# BabyBeat.net
KiCad netlist of a schematic drawn in EAGLE
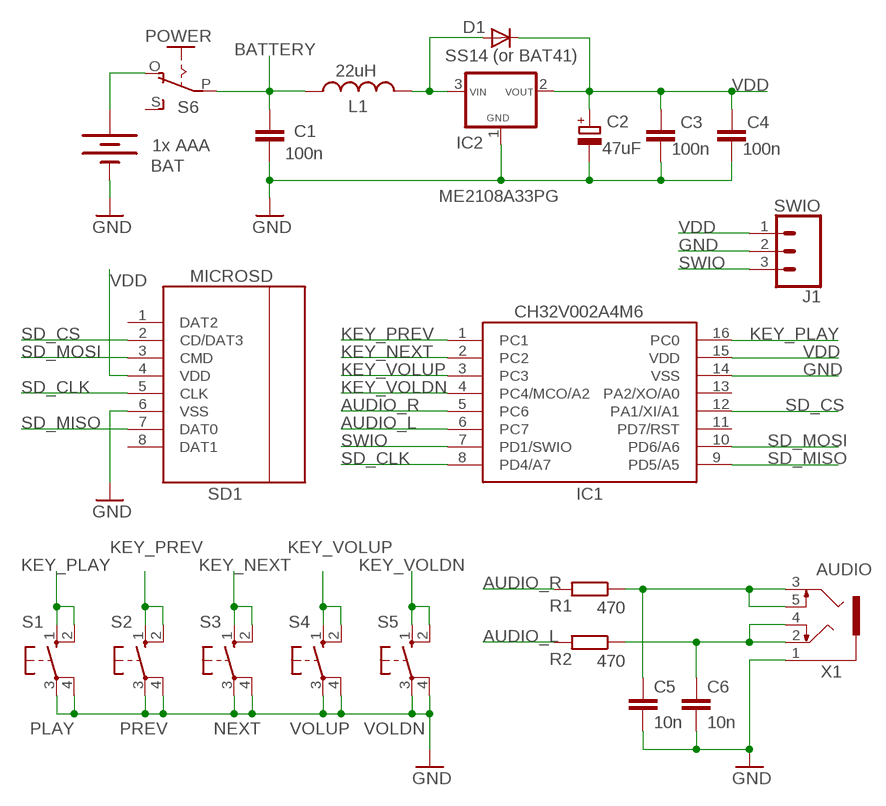
[diagram p0: schematic, sheet 1]

(export (version "E")
  (design (tool "Eeschema 10.0.6"))
  (components
    (comp (ref "BAT")
      (value "1x AAA")
      (footprint "eagle-import:BATTERY-AAA-KIT")
      (libsource (lib "eagle-import") (part "BATTERY-AAA_KIT"))
    )
    (comp (ref "C1")
      (value "100n")
      (footprint "eagle-import:C1206K")
      (libsource (lib "eagle-import") (part "C-EUC1206K"))
    )
    (comp (ref "C2")
      (value "47uF")
      (footprint "eagle-import:140CLH-0810")
      (libsource (lib "eagle-import") (part "CPOL-EU140CLH-0810"))
    )
    (comp (ref "C3")
      (value "100n")
      (footprint "eagle-import:C1206K")
      (libsource (lib "eagle-import") (part "C-EUC1206K"))
    )
    (comp (ref "C4")
      (value "100n")
      (footprint "eagle-import:C1206K")
      (libsource (lib "eagle-import") (part "C-EUC1206K"))
    )
    (comp (ref "C5")
      (value "10n")
      (footprint "eagle-import:C1206K")
      (libsource (lib "eagle-import") (part "C-EUC1206K"))
    )
    (comp (ref "C6")
      (value "10n")
      (footprint "eagle-import:C1206K")
      (libsource (lib "eagle-import") (part "C-EUC1206K"))
    )
    (comp (ref "D1")
      (value "SS14 (or BAT41)")
      (footprint "eagle-import:SOD-123_MINI-SMA")
      (libsource (lib "eagle-import") (part "CGRM400-G1"))
    )
    (comp (ref "IC1")
      (value "CH32V002A4M6")
      (footprint "eagle-import:SOP16")
      (libsource (lib "eagle-import") (part "CH32V002A4M6"))
    )
    (comp (ref "IC2")
      (value "ME2108A33PG")
      (footprint "eagle-import:SOT89-R")
      (libsource (lib "eagle-import") (part "ME2108A33PG"))
    )
    (comp (ref "J1")
      (value "SWIO")
      (footprint "eagle-import:1X03_LONGPADS")
      (libsource (lib "eagle-import") (part "CONN_03LONGPADS"))
    )
    (comp (ref "L1")
      (value "22uH")
      (footprint "eagle-import:POWER-CHOKE_WE-TPC")
      (libsource (lib "eagle-import") (part "L-USWE-TPC"))
    )
    (comp (ref "R1")
      (value "470")
      (footprint "eagle-import:M1206")
      (libsource (lib "eagle-import") (part "R-EU_M1206"))
    )
    (comp (ref "R2")
      (value "470")
      (footprint "eagle-import:M1206")
      (libsource (lib "eagle-import") (part "R-EU_M1206"))
    )
    (comp (ref "S1")
      (value "PLAY")
      (footprint "eagle-import:B3F-10XX")
      (fields (field (name "MPN") "B3F-1000"))
      (libsource (lib "eagle-import") (part "10-XX"))
    )
    (comp (ref "S2")
      (value "PREV")
      (footprint "eagle-import:B3F-10XX")
      (fields (field (name "MPN") "B3F-1000"))
      (libsource (lib "eagle-import") (part "10-XX"))
    )
    (comp (ref "S3")
      (value "NEXT")
      (footprint "eagle-import:B3F-10XX")
      (fields (field (name "MPN") "B3F-1000"))
      (libsource (lib "eagle-import") (part "10-XX"))
    )
    (comp (ref "S4")
      (value "VOLUP")
      (footprint "eagle-import:B3F-10XX")
      (fields (field (name "MPN") "B3F-1000"))
      (libsource (lib "eagle-import") (part "10-XX"))
    )
    (comp (ref "S5")
      (value "VOLDN")
      (footprint "eagle-import:B3F-10XX")
      (fields (field (name "MPN") "B3F-1000"))
      (libsource (lib "eagle-import") (part "10-XX"))
    )
    (comp (ref "S6")
      (value "POWER")
      (footprint "eagle-import:EG1218")
      (libsource (lib "eagle-import") (part "EG1218S"))
    )
    (comp (ref "SD1")
      (value "MICROSD")
      (footprint "eagle-import:MICROSD")
      (libsource (lib "eagle-import") (part "MICROSD"))
    )
    (comp (ref "X1")
      (value "AUDIO")
      (footprint "eagle-import:1503_09")
      (libsource (lib "eagle-import") (part "1503_09"))
    )
  )
  (nets
    (net (code "1") (name "/AUDIO_L") (class "Default")
      (node (ref "IC1") (pin "6") (pinfunction "PC7_6") (pintype "bidirectional"))
      (node (ref "R2") (pin "2") (pinfunction "2_2") (pintype "passive"))
    )
    (net (code "2") (name "/AUDIO_R") (class "Default")
      (node (ref "IC1") (pin "5") (pinfunction "PC6_5") (pintype "bidirectional"))
      (node (ref "R1") (pin "2") (pinfunction "2_2") (pintype "passive"))
    )
    (net (code "3") (name "/BATTERY") (class "Default")
      (node (ref "C1") (pin "1") (pinfunction "1_1") (pintype "passive"))
      (node (ref "L1") (pin "1") (pinfunction "1_1") (pintype "passive"))
      (node (ref "S6") (pin "P") (pinfunction "P_P") (pintype "passive"))
    )
    (net (code "4") (name "/KEY_NEXT") (class "Default")
      (node (ref "IC1") (pin "2") (pinfunction "PC2_2") (pintype "bidirectional"))
      (node (ref "S3") (pin "1") (pinfunction "S_1") (pintype "passive"))
      (node (ref "S3") (pin "2") (pinfunction "S1_2") (pintype "passive"))
    )
    (net (code "5") (name "/KEY_PLAY") (class "Default")
      (node (ref "IC1") (pin "16") (pinfunction "PC0_16") (pintype "bidirectional"))
      (node (ref "S1") (pin "1") (pinfunction "S_1") (pintype "passive"))
      (node (ref "S1") (pin "2") (pinfunction "S1_2") (pintype "passive"))
    )
    (net (code "6") (name "/KEY_PREV") (class "Default")
      (node (ref "IC1") (pin "1") (pinfunction "PC1_1") (pintype "bidirectional"))
      (node (ref "S2") (pin "1") (pinfunction "S_1") (pintype "passive"))
      (node (ref "S2") (pin "2") (pinfunction "S1_2") (pintype "passive"))
    )
    (net (code "7") (name "/KEY_VOLDN") (class "Default")
      (node (ref "IC1") (pin "4") (pinfunction "PC4/MCO/A2_4") (pintype "bidirectional"))
      (node (ref "S5") (pin "1") (pinfunction "S_1") (pintype "passive"))
      (node (ref "S5") (pin "2") (pinfunction "S1_2") (pintype "passive"))
    )
    (net (code "8") (name "/KEY_VOLUP") (class "Default")
      (node (ref "IC1") (pin "3") (pinfunction "PC3_3") (pintype "bidirectional"))
      (node (ref "S4") (pin "1") (pinfunction "S_1") (pintype "passive"))
      (node (ref "S4") (pin "2") (pinfunction "S1_2") (pintype "passive"))
    )
    (net (code "9") (name "/SD_CLK") (class "Default")
      (node (ref "IC1") (pin "8") (pinfunction "PD4/A7_8") (pintype "bidirectional"))
      (node (ref "SD1") (pin "5") (pinfunction "CLK_5") (pintype "bidirectional"))
    )
    (net (code "10") (name "/SD_CS") (class "Default")
      (node (ref "IC1") (pin "12") (pinfunction "PA1/XI/A1_12") (pintype "bidirectional"))
      (node (ref "SD1") (pin "2") (pinfunction "CD/DAT3_2") (pintype "bidirectional"))
    )
    (net (code "11") (name "/SD_MISO") (class "Default")
      (node (ref "IC1") (pin "9") (pinfunction "PD5/A5_9") (pintype "bidirectional"))
      (node (ref "SD1") (pin "7") (pinfunction "DAT0_7") (pintype "bidirectional"))
    )
    (net (code "12") (name "/SD_MOSI") (class "Default")
      (node (ref "IC1") (pin "10") (pinfunction "PD6/A6_10") (pintype "bidirectional"))
      (node (ref "SD1") (pin "3") (pinfunction "CMD_3") (pintype "bidirectional"))
    )
    (net (code "13") (name "/SWIO") (class "Default")
      (node (ref "IC1") (pin "7") (pinfunction "PD1/SWIO_7") (pintype "bidirectional"))
      (node (ref "J1") (pin "3") (pinfunction "3_3") (pintype "passive"))
    )
    (net (code "14") (name "/VDD") (class "Default")
      (node (ref "C2") (pin "+") (pinfunction "+_+") (pintype "passive"))
      (node (ref "C3") (pin "1") (pinfunction "1_1") (pintype "passive"))
      (node (ref "C4") (pin "1") (pinfunction "1_1") (pintype "passive"))
      (node (ref "D1") (pin "C") (pinfunction "C_C") (pintype "passive"))
      (node (ref "IC1") (pin "15") (pinfunction "VDD_15") (pintype "power_in"))
      (node (ref "IC2") (pin "2") (pinfunction "VOUT_2") (pintype "power_in"))
      (node (ref "J1") (pin "1") (pinfunction "1_1") (pintype "passive"))
      (node (ref "SD1") (pin "4") (pinfunction "VDD_4") (pintype "bidirectional"))
    )
    (net (code "15") (name "GND") (class "Default")
      (node (ref "BAT") (pin "GND@1") (pinfunction "-_GND@1") (pintype "power_in"))
      (node (ref "C1") (pin "2") (pinfunction "2_2") (pintype "passive"))
      (node (ref "C2") (pin "-") (pinfunction "-_-") (pintype "passive"))
      (node (ref "C3") (pin "2") (pinfunction "2_2") (pintype "passive"))
      (node (ref "C4") (pin "2") (pinfunction "2_2") (pintype "passive"))
      (node (ref "C5") (pin "2") (pinfunction "2_2") (pintype "passive"))
      (node (ref "C6") (pin "2") (pinfunction "2_2") (pintype "passive"))
      (node (ref "IC1") (pin "14") (pinfunction "VSS_14") (pintype "power_in"))
      (node (ref "IC2") (pin "1") (pinfunction "GND_1") (pintype "power_in"))
      (node (ref "J1") (pin "2") (pinfunction "2_2") (pintype "passive"))
      (node (ref "S1") (pin "3") (pinfunction "P_3") (pintype "passive"))
      (node (ref "S1") (pin "4") (pinfunction "P1_4") (pintype "passive"))
      (node (ref "S2") (pin "3") (pinfunction "P_3") (pintype "passive"))
      (node (ref "S2") (pin "4") (pinfunction "P1_4") (pintype "passive"))
      (node (ref "S3") (pin "3") (pinfunction "P_3") (pintype "passive"))
      (node (ref "S3") (pin "4") (pinfunction "P1_4") (pintype "passive"))
      (node (ref "S4") (pin "3") (pinfunction "P_3") (pintype "passive"))
      (node (ref "S4") (pin "4") (pinfunction "P1_4") (pintype "passive"))
      (node (ref "S5") (pin "3") (pinfunction "P_3") (pintype "passive"))
      (node (ref "S5") (pin "4") (pinfunction "P1_4") (pintype "passive"))
      (node (ref "SD1") (pin "6") (pinfunction "VSS_6") (pintype "bidirectional"))
      (node (ref "X1") (pin "1") (pinfunction "1_1") (pintype "passive"))
    )
    (net (code "16") (name "Net-(BAT-+)") (class "Default")
      (node (ref "BAT") (pin "PWR@1") (pinfunction "+_PWR@1") (pintype "power_in"))
      (node (ref "S6") (pin "O") (pinfunction "O_O") (pintype "passive"))
    )
    (net (code "17") (name "Net-(C5-Pad1)") (class "Default")
      (node (ref "C5") (pin "1") (pinfunction "1_1") (pintype "passive"))
      (node (ref "R1") (pin "1") (pinfunction "1_1") (pintype "passive"))
      (node (ref "X1") (pin "3") (pinfunction "3_3") (pintype "passive"))
      (node (ref "X1") (pin "5") (pinfunction "5_5") (pintype "passive"))
    )
    (net (code "18") (name "Net-(C6-Pad1)") (class "Default")
      (node (ref "C6") (pin "1") (pinfunction "1_1") (pintype "passive"))
      (node (ref "R2") (pin "1") (pinfunction "1_1") (pintype "passive"))
      (node (ref "X1") (pin "2") (pinfunction "2_2") (pintype "passive"))
      (node (ref "X1") (pin "4") (pinfunction "4_4") (pintype "passive"))
    )
    (net (code "19") (name "Net-(IC2-IN)") (class "Default")
      (node (ref "D1") (pin "A") (pinfunction "A_A") (pintype "passive"))
      (node (ref "IC2") (pin "3") (pinfunction "IN_3") (pintype "power_in"))
      (node (ref "L1") (pin "2") (pinfunction "2_2") (pintype "passive"))
    )
    (net (code "20") (name "unconnected-(IC1-PA2{slash}XO{slash}A0-Pad13)") (class "Default")
      (node (ref "IC1") (pin "13") (pinfunction "PA2/XO/A0_13") (pintype "bidirectional"))
    )
    (net (code "21") (name "unconnected-(IC1-PD7{slash}RST-Pad11)") (class "Default")
      (node (ref "IC1") (pin "11") (pinfunction "PD7/RST_11") (pintype "bidirectional"))
    )
    (net (code "22") (name "unconnected-(S6-PadS)") (class "Default")
      (node (ref "S6") (pin "S") (pinfunction "S_S") (pintype "passive"))
    )
    (net (code "23") (name "unconnected-(SD1-DAT1-Pad8)") (class "Default")
      (node (ref "SD1") (pin "8") (pinfunction "DAT1_8") (pintype "bidirectional"))
    )
    (net (code "24") (name "unconnected-(SD1-DAT2-Pad1)") (class "Default")
      (node (ref "SD1") (pin "1") (pinfunction "DAT2_1") (pintype "bidirectional"))
    )
  )
)
